# PG04_SHEET2.net
KiCad netlist of a schematic drawn in Altium Designer
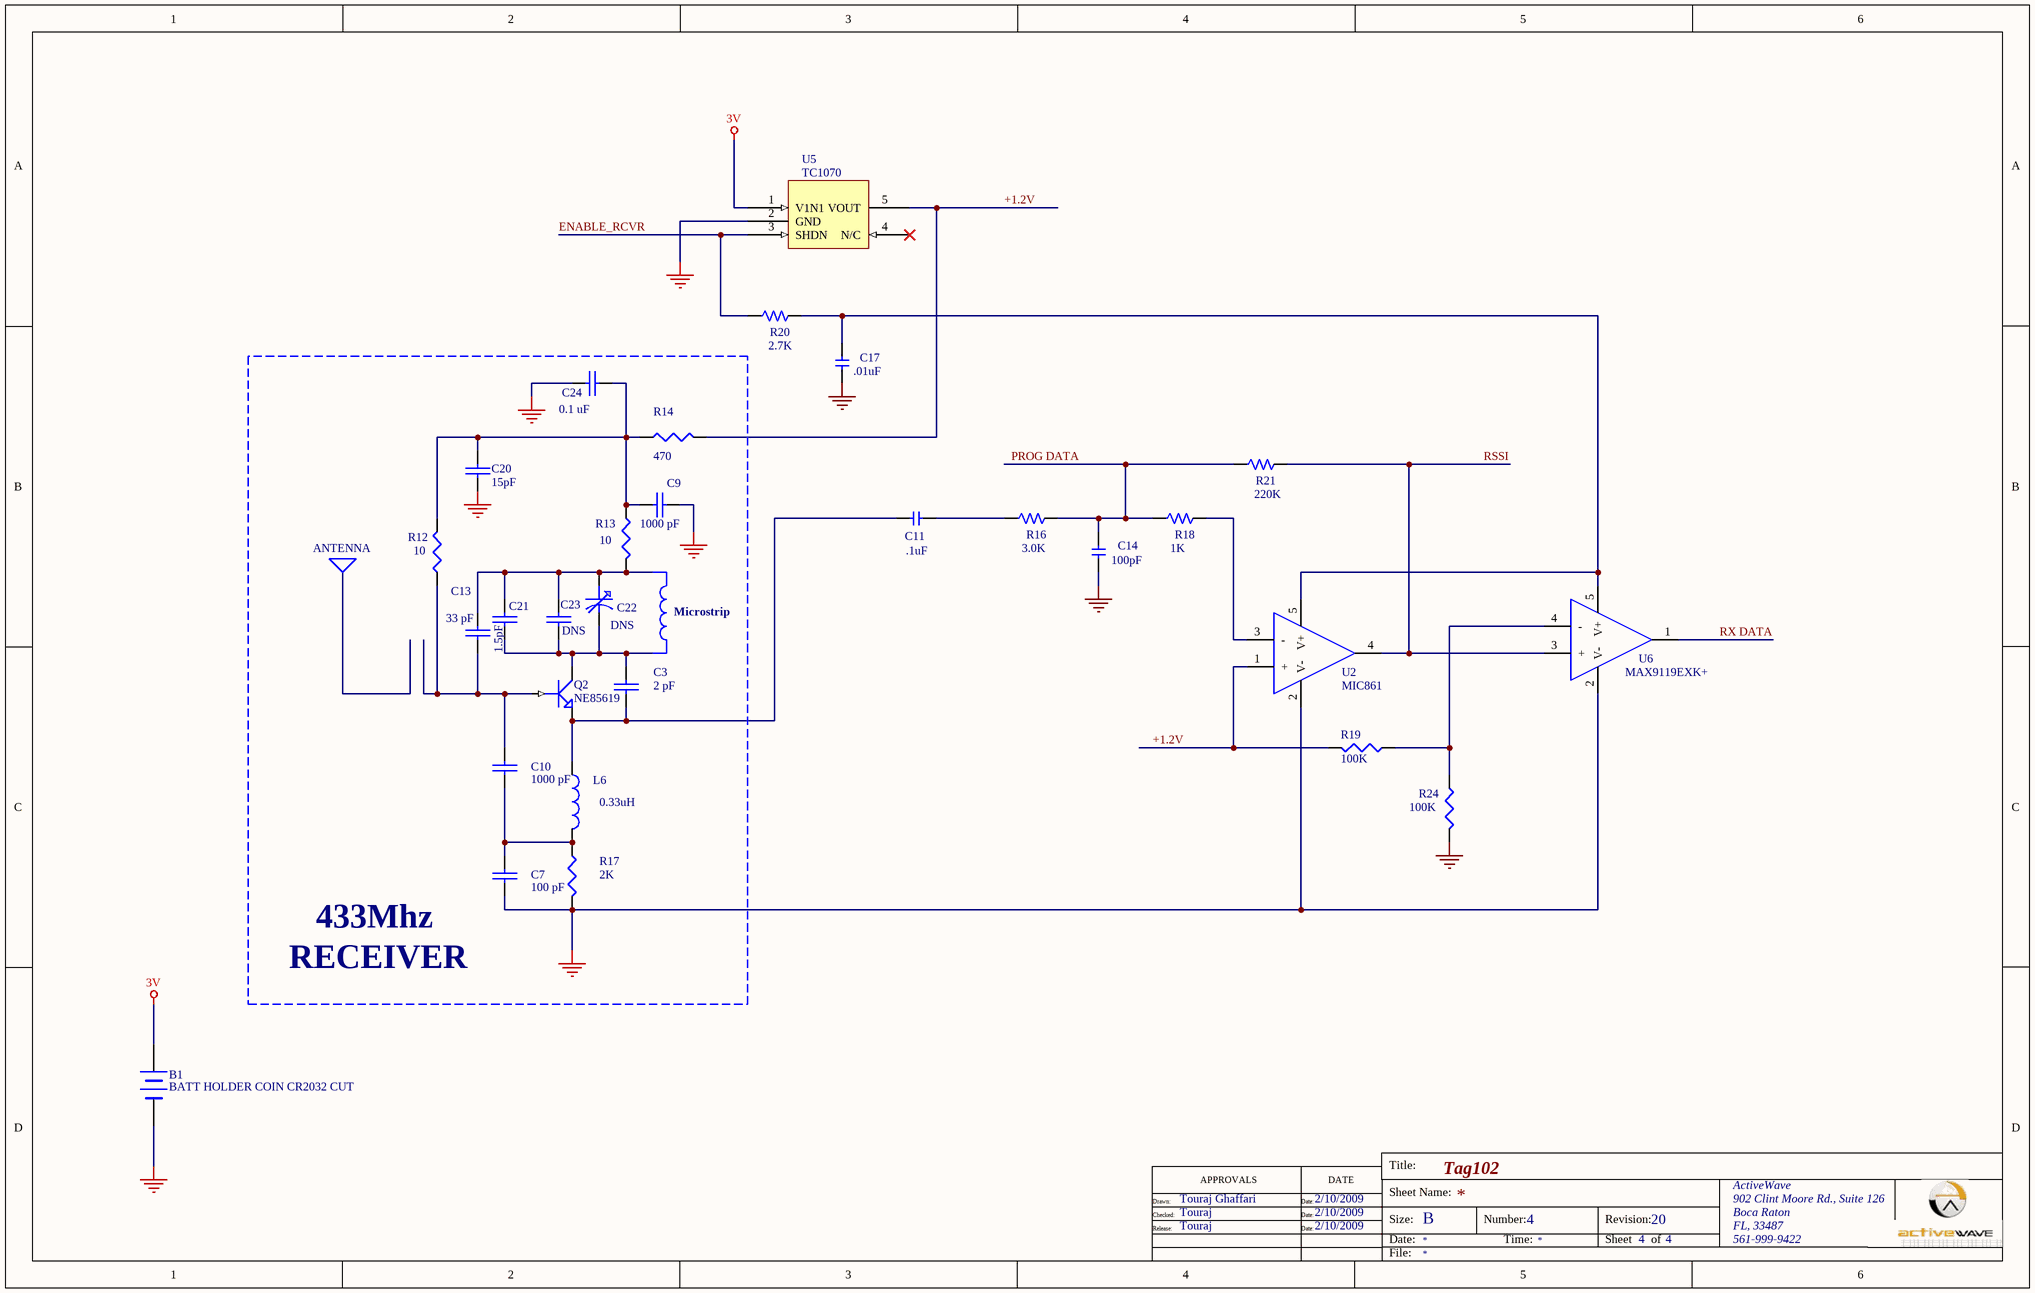
[diagram p0: PG04 SHEET2.schdoc]

(export (version "E")
  (design (tool "Eeschema 10.0.6"))
  (components
    (comp (ref "B1")
      (value "BATT HOLDER COIN CR2032 CUT")
      (footprint "BATT HOLDER COIN CR2032 CUT_020812")
      (description "Battery")
      (libsource (lib "*") (part "BATTERY"))
    )
    (comp (ref "C3")
      (value "2 pF")
      (footprint "0603")
      (description "Capacitor")
      (libsource (lib "*") (part "CAP"))
    )
    (comp (ref "C7")
      (value "100 pF")
      (footprint "0603")
      (description "Capacitor")
      (libsource (lib "*") (part "CAP"))
    )
    (comp (ref "C9")
      (value "1000 pF")
      (footprint "0603")
      (description "Capacitor")
      (libsource (lib "*") (part "CAP"))
    )
    (comp (ref "C10")
      (value "1000 pF")
      (footprint "0603")
      (description "Capacitor")
      (libsource (lib "*") (part "CAP"))
    )
    (comp (ref "C11") (value ".1uF") (footprint "0603") (libsource (lib "*") (part "C")))
    (comp (ref "C13")
      (value "33 pF")
      (footprint "0603")
      (description "Capacitor")
      (libsource (lib "*") (part "CAP"))
    )
    (comp (ref "C14") (value "100pF") (footprint "0603") (libsource (lib "*") (part "C")))
    (comp (ref "C17") (value ".01uF") (footprint "0603") (libsource (lib "*") (part "C")))
    (comp (ref "C20")
      (value "15pF")
      (footprint "0603")
      (description "Capacitor")
      (libsource (lib "*") (part "CAP"))
    )
    (comp (ref "C21")
      (value "1.5pF")
      (footprint "0603")
      (description "Capacitor")
      (libsource (lib "*") (part "CAP"))
    )
    (comp (ref "C22") (value "DNS") (footprint "0603") (libsource (lib "*") (part "CAPACITOR VAR")))
    (comp (ref "C23")
      (value "DNS")
      (footprint "0603")
      (description "Capacitor")
      (libsource (lib "*") (part "CAP"))
    )
    (comp (ref "C24")
      (value "0.1 uF")
      (footprint "0603")
      (description "Capacitor")
      (libsource (lib "*") (part "CAP"))
    )
    (comp (ref "L6") (value "0.33uH") (footprint "0603") (libsource (lib "*") (part "INDUCTOR")))
    (comp (ref "Q2")
      (value "NE85619")
      (footprint "3 PIN ULTRA SUPER MINI MOLD")
      (description "NPN Transistor")
      (libsource (lib "*") (part "NPN1"))
    )
    (comp (ref "R12") (value "10") (footprint "0603") (libsource (lib "") (part "R_1")))
    (comp (ref "R13") (value "10") (footprint "0603") (libsource (lib "") (part "R_1")))
    (comp (ref "R14") (value "470") (footprint "0603") (libsource (lib "") (part "R_1")))
    (comp (ref "R16") (value "3.0K") (footprint "0603") (libsource (lib "*") (part "R")))
    (comp (ref "R17") (value "2K") (footprint "0603") (libsource (lib "*") (part "RESISTOR")))
    (comp (ref "R18") (value "1K") (footprint "0603") (libsource (lib "*") (part "R")))
    (comp (ref "R19") (value "100K") (footprint "0603") (libsource (lib "") (part "R_1")))
    (comp (ref "R20") (value "2.7K") (footprint "0603") (libsource (lib "*") (part "R")))
    (comp (ref "R21") (value "220K") (footprint "0603") (libsource (lib "*") (part "R")))
    (comp (ref "R24") (value "100K") (footprint "0603") (libsource (lib "") (part "R_1")))
    (comp (ref "U2") (value "MIC861") (footprint "SC70") (libsource (lib "*") (part "OPAMP MIC861")))
    (comp (ref "U5") (value "TC1070") (footprint "SOT23-5A") (libsource (lib "*") (part "TC1070-2")))
    (comp (ref "U6")
      (value "MAX9119EXK+")
      (footprint "SC70")
      (libsource (lib "*") (part "COMPARATOR MAX9117"))
    )
  )
  (nets
    (net (code "1") (name "/+1.2V") (class "Default")
      (node (ref "R14") (pin "2") (pinfunction "2_2") (pintype "passive"))
      (node (ref "R19") (pin "2") (pinfunction "2_2") (pintype "passive"))
      (node (ref "U2") (pin "1") (pinfunction "+_1") (pintype "passive"))
      (node (ref "U5") (pin "5") (pinfunction "VOUT_5") (pintype "power_in"))
    )
    (net (code "2") (name "/ENABLE_RCVR") (class "Default")
      (node (ref "R20") (pin "1") (pinfunction "1_1") (pintype "passive"))
      (node (ref "U5") (pin "3") (pinfunction "SHDN_3") (pintype "input"))
    )
    (net (code "3") (name "/PROG DATA") (class "Default")
      (node (ref "C14") (pin "2") (pinfunction "2_2") (pintype "passive"))
      (node (ref "R16") (pin "2") (pinfunction "2_2") (pintype "passive"))
      (node (ref "R18") (pin "1") (pinfunction "1_1") (pintype "passive"))
      (node (ref "R21") (pin "1") (pinfunction "1_1") (pintype "passive"))
    )
    (net (code "4") (name "/RSSI") (class "Default")
      (node (ref "R21") (pin "2") (pinfunction "2_2") (pintype "passive"))
      (node (ref "U2") (pin "4") (pinfunction "OUT_4") (pintype "passive"))
      (node (ref "U6") (pin "3") (pinfunction "+_3") (pintype "passive"))
    )
    (net (code "5") (name "/RX DATA") (class "Default")
      (node (ref "U6") (pin "1") (pinfunction "OUT_1") (pintype "passive"))
    )
    (net (code "6") (name "3V") (class "Default")
      (node (ref "B1") (pin "2") (pinfunction "+_2") (pintype "passive"))
      (node (ref "U5") (pin "1") (pinfunction "V1N1_1") (pintype "input"))
    )
    (net (code "7") (name "GND") (class "Default")
      (node (ref "B1") (pin "1") (pinfunction "-_1") (pintype "passive"))
      (node (ref "C14") (pin "1") (pinfunction "1_1") (pintype "passive"))
      (node (ref "C17") (pin "1") (pinfunction "1_1") (pintype "passive"))
      (node (ref "C20") (pin "1") (pinfunction "1_1") (pintype "passive"))
      (node (ref "C24") (pin "1") (pinfunction "1_1") (pintype "passive"))
      (node (ref "C7") (pin "2") (pinfunction "2_2") (pintype "passive"))
      (node (ref "C9") (pin "2") (pinfunction "2_2") (pintype "passive"))
      (node (ref "R17") (pin "2") (pinfunction "2_2") (pintype "passive"))
      (node (ref "R24") (pin "2") (pinfunction "2_2") (pintype "passive"))
      (node (ref "U2") (pin "2") (pinfunction "V-_2") (pintype "passive"))
      (node (ref "U5") (pin "2") (pinfunction "GND_2") (pintype "power_in"))
      (node (ref "U6") (pin "2") (pinfunction "V-_2") (pintype "passive"))
    )
    (net (code "8") (name "Net-(C10-Pad1)") (class "Default")
      (node (ref "C10") (pin "1") (pinfunction "1_1") (pintype "passive"))
      (node (ref "C13") (pin "1") (pinfunction "1_1") (pintype "passive"))
      (node (ref "Q2") (pin "B") (pinfunction "B_B") (pintype "input"))
      (node (ref "R12") (pin "1") (pinfunction "1_1") (pintype "passive"))
    )
    (net (code "9") (name "Net-(C10-Pad2)") (class "Default")
      (node (ref "C10") (pin "2") (pinfunction "2_2") (pintype "passive"))
      (node (ref "C7") (pin "1") (pinfunction "1_1") (pintype "passive"))
      (node (ref "L6") (pin "2") (pinfunction "2_2") (pintype "passive"))
      (node (ref "R17") (pin "1") (pinfunction "1_1") (pintype "passive"))
    )
    (net (code "10") (name "Net-(C11-Pad1)") (class "Default")
      (node (ref "C11") (pin "1") (pinfunction "1_1") (pintype "passive"))
      (node (ref "C3") (pin "2") (pinfunction "2_2") (pintype "passive"))
      (node (ref "L6") (pin "1") (pinfunction "1_1") (pintype "passive"))
      (node (ref "Q2") (pin "E") (pinfunction "E_E") (pintype "passive"))
    )
    (net (code "11") (name "Net-(C11-Pad2)") (class "Default")
      (node (ref "C11") (pin "2") (pinfunction "2_2") (pintype "passive"))
      (node (ref "R16") (pin "1") (pinfunction "1_1") (pintype "passive"))
    )
    (net (code "12") (name "Net-(C13-Pad2)") (class "Default")
      (node (ref "C13") (pin "2") (pinfunction "2_2") (pintype "passive"))
      (node (ref "C21") (pin "1") (pinfunction "1_1") (pintype "passive"))
      (node (ref "C22") (pin "1") (pinfunction "1_1") (pintype "passive"))
      (node (ref "C23") (pin "1") (pinfunction "1_1") (pintype "passive"))
      (node (ref "R13") (pin "2") (pinfunction "2_2") (pintype "passive"))
    )
    (net (code "13") (name "Net-(C20-Pad2)") (class "Default")
      (node (ref "C20") (pin "2") (pinfunction "2_2") (pintype "passive"))
      (node (ref "C24") (pin "2") (pinfunction "2_2") (pintype "passive"))
      (node (ref "C9") (pin "1") (pinfunction "1_1") (pintype "passive"))
      (node (ref "R12") (pin "2") (pinfunction "2_2") (pintype "passive"))
      (node (ref "R13") (pin "1") (pinfunction "1_1") (pintype "passive"))
      (node (ref "R14") (pin "1") (pinfunction "1_1") (pintype "passive"))
    )
    (net (code "14") (name "Net-(C21-Pad2)") (class "Default")
      (node (ref "C21") (pin "2") (pinfunction "2_2") (pintype "passive"))
      (node (ref "C22") (pin "2") (pinfunction "2_2") (pintype "passive"))
      (node (ref "C23") (pin "2") (pinfunction "2_2") (pintype "passive"))
      (node (ref "C3") (pin "1") (pinfunction "1_1") (pintype "passive"))
      (node (ref "Q2") (pin "C") (pinfunction "C_C") (pintype "passive"))
    )
    (net (code "15") (name "Net-(U2--)") (class "Default")
      (node (ref "R18") (pin "2") (pinfunction "2_2") (pintype "passive"))
      (node (ref "U2") (pin "3") (pinfunction "-_3") (pintype "passive"))
    )
    (net (code "16") (name "Net-(U2-V+)") (class "Default")
      (node (ref "C17") (pin "2") (pinfunction "2_2") (pintype "passive"))
      (node (ref "R20") (pin "2") (pinfunction "2_2") (pintype "passive"))
      (node (ref "U2") (pin "5") (pinfunction "V+_5") (pintype "passive"))
      (node (ref "U6") (pin "5") (pinfunction "V+_5") (pintype "passive"))
    )
    (net (code "17") (name "Net-(U6--)") (class "Default")
      (node (ref "R19") (pin "1") (pinfunction "1_1") (pintype "passive"))
      (node (ref "R24") (pin "1") (pinfunction "1_1") (pintype "passive"))
      (node (ref "U6") (pin "4") (pinfunction "-_4") (pintype "passive"))
    )
    (net (code "18") (name "unconnected-(U5-N{slash}C-Pad4)") (class "Default")
      (node (ref "U5") (pin "4") (pinfunction "N/C_4") (pintype "input+no_connect"))
    )
  )
)
